# GPS_lte2.net
KiCad netlist of a schematic drawn in Altium Designer
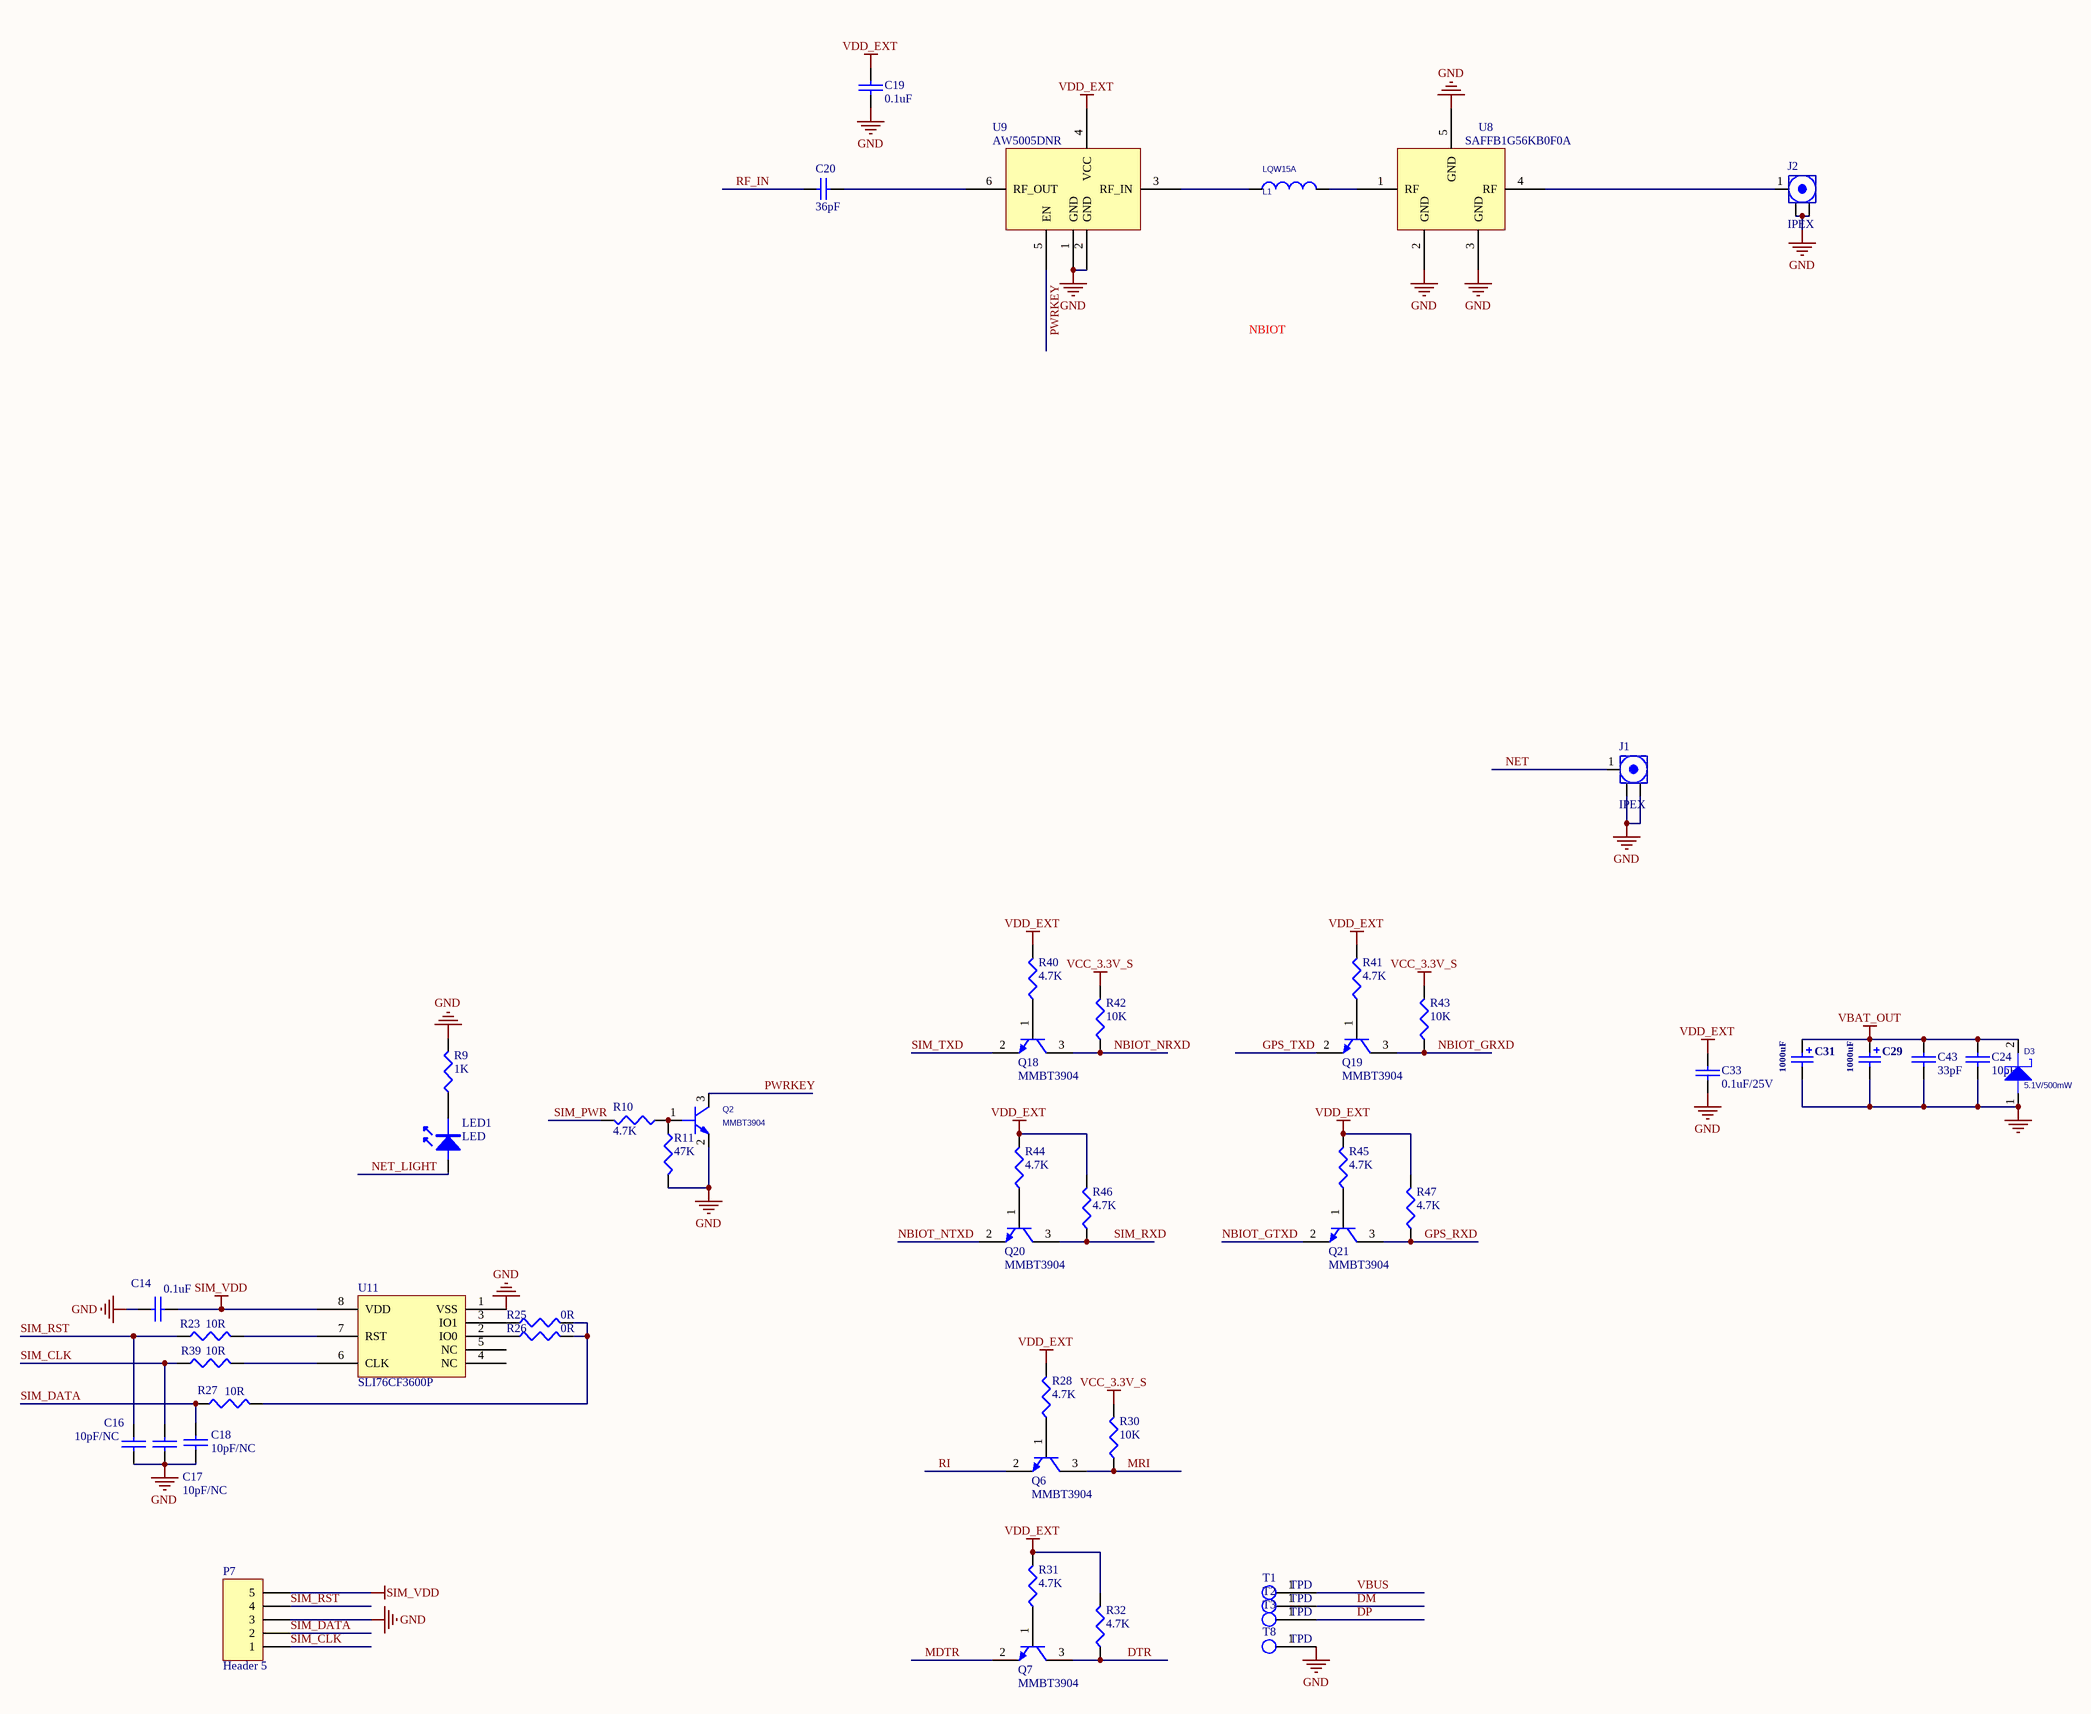
[diagram p0: GPS&&lte2.SchDoc]

(export (version "E")
  (design (tool "Eeschema 10.0.6"))
  (components
    (comp (ref "C14")
      (value "0.1uF")
      (footprint "0402C")
      (description "Capacitor")
      (libsource (lib "ZWLIntegrated_Library") (part "CAP"))
    )
    (comp (ref "C16")
      (value "10pF/NC")
      (footprint "0402C")
      (description "Capacitor")
      (libsource (lib "ZWLIntegrated_Library") (part "CAP"))
    )
    (comp (ref "C17")
      (value "10pF/NC")
      (footprint "0402C")
      (description "Capacitor")
      (libsource (lib "ZWLIntegrated_Library") (part "CAP"))
    )
    (comp (ref "C18")
      (value "10pF/NC")
      (footprint "0402C")
      (description "Capacitor")
      (libsource (lib "ZWLIntegrated_Library") (part "CAP"))
    )
    (comp (ref "C19")
      (value "0.1uF")
      (footprint "0402C")
      (description "Capacitor")
      (libsource (lib "ZWLIntegrated_Library") (part "CAP"))
    )
    (comp (ref "C20")
      (value "36pF")
      (footprint "0402c")
      (description "Capacitor")
      (fields (field (name "PUBLISHER") "Altium Limited"))
      (libsource (lib "Miscellaneous Devices") (part "Cap"))
    )
    (comp (ref "C24")
      (value "10pF")
      (footprint "0402C")
      (description "Capacitor")
      (libsource (lib "ZWLIntegrated_Library") (part "CAP"))
    )
    (comp (ref "C29")
      (value "1000uF")
      (footprint "7343")
      (description "Polarized Capacitor (Surface Mount)")
      (libsource (lib "KT_iBeacon") (part "Cap Pol3"))
    )
    (comp (ref "C31")
      (value "1000uF")
      (footprint "7343")
      (description "Polarized Capacitor (Surface Mount)")
      (libsource (lib "KT_iBeacon") (part "Cap Pol3"))
    )
    (comp (ref "C33")
      (value "0.1uF/25V")
      (footprint "0402C")
      (description "Capacitor")
      (libsource (lib "ZWLIntegrated_Library") (part "CAP"))
    )
    (comp (ref "C43")
      (value "33pF")
      (footprint "0402C")
      (description "Capacitor")
      (libsource (lib "ZWLIntegrated_Library") (part "CAP"))
    )
    (comp (ref "D3")
      (value "5.1V/500mW")
      (footprint "LL-34(D1206)")
      (fields (field (name "Comment") "DIODE_SCHOTTKY_0"))
      (libsource (lib "KT_iBeacon") (part "DIODE_SCHOTTKY_0"))
    )
    (comp (ref "J1") (value "IPEX") (footprint "RF-UFL") (libsource (lib "我的元件库") (part "ANT")))
    (comp (ref "J2") (value "IPEX") (footprint "RF-UFL") (libsource (lib "我的元件库") (part "ANT")))
    (comp (ref "L1") (value "LQW15A") (footprint "0402R") (libsource (lib "*") (part "INDUCTOR_1")))
    (comp (ref "LED1") (value "LED") (footprint "0603LED") (libsource (lib "我的元件库") (part "LED")))
    (comp (ref "P7")
      (value "Header 5")
      (footprint "5×1.25mmSMT")
      (description "Header, 5-Pin")
      (fields (field (name "PUBLISHER") "Altium Limited"))
      (libsource (lib "Miscellaneous Connectors") (part "Header 5"))
    )
    (comp (ref "Q2") (value "MMBT3904") (footprint "SOT23-3") (libsource (lib "*") (part "2N1069_1")))
    (comp (ref "Q6") (value "MMBT3904") (footprint "SOT23-3") (libsource (lib "Schlib1") (part "NPN")))
    (comp (ref "Q7") (value "MMBT3904") (footprint "SOT23-3") (libsource (lib "Schlib1") (part "NPN")))
    (comp (ref "Q18") (value "MMBT3904") (footprint "SOT23-3") (libsource (lib "Schlib1") (part "NPN")))
    (comp (ref "Q19") (value "MMBT3904") (footprint "SOT23-3") (libsource (lib "Schlib1") (part "NPN")))
    (comp (ref "Q20") (value "MMBT3904") (footprint "SOT23-3") (libsource (lib "Schlib1") (part "NPN")))
    (comp (ref "Q21") (value "MMBT3904") (footprint "SOT23-3") (libsource (lib "Schlib1") (part "NPN")))
    (comp (ref "R9") (value "1K") (footprint "0402R") (libsource (lib "ZWLIntegrated_Library") (part "RES1")))
    (comp (ref "R10")
      (value "4.7K")
      (footprint "0402R")
      (libsource (lib "ZWLIntegrated_Library") (part "RES1"))
    )
    (comp (ref "R11")
      (value "47K")
      (footprint "0402R")
      (libsource (lib "ZWLIntegrated_Library") (part "RES1"))
    )
    (comp (ref "R23")
      (value "10R")
      (footprint "0402R")
      (libsource (lib "ZWLIntegrated_Library") (part "RES1"))
    )
    (comp (ref "R25")
      (value "0R")
      (footprint "0402R")
      (libsource (lib "ZWLIntegrated_Library") (part "RES1"))
    )
    (comp (ref "R26")
      (value "0R")
      (footprint "0402R")
      (libsource (lib "ZWLIntegrated_Library") (part "RES1"))
    )
    (comp (ref "R27")
      (value "10R")
      (footprint "0402R")
      (libsource (lib "ZWLIntegrated_Library") (part "RES1"))
    )
    (comp (ref "R28")
      (value "4.7K")
      (footprint "0402R")
      (libsource (lib "ZWLIntegrated_Library") (part "RES1"))
    )
    (comp (ref "R30")
      (value "10K")
      (footprint "0402R")
      (libsource (lib "ZWLIntegrated_Library") (part "RES1"))
    )
    (comp (ref "R31")
      (value "4.7K")
      (footprint "0402R")
      (libsource (lib "ZWLIntegrated_Library") (part "RES1"))
    )
    (comp (ref "R32")
      (value "4.7K")
      (footprint "0402R")
      (libsource (lib "ZWLIntegrated_Library") (part "RES1"))
    )
    (comp (ref "R39")
      (value "10R")
      (footprint "0402R")
      (libsource (lib "ZWLIntegrated_Library") (part "RES1"))
    )
    (comp (ref "R40")
      (value "4.7K")
      (footprint "0402R")
      (libsource (lib "ZWLIntegrated_Library") (part "RES1"))
    )
    (comp (ref "R41")
      (value "4.7K")
      (footprint "0402R")
      (libsource (lib "ZWLIntegrated_Library") (part "RES1"))
    )
    (comp (ref "R42")
      (value "10K")
      (footprint "0402R")
      (libsource (lib "ZWLIntegrated_Library") (part "RES1"))
    )
    (comp (ref "R43")
      (value "10K")
      (footprint "0402R")
      (libsource (lib "ZWLIntegrated_Library") (part "RES1"))
    )
    (comp (ref "R44")
      (value "4.7K")
      (footprint "0402R")
      (libsource (lib "ZWLIntegrated_Library") (part "RES1"))
    )
    (comp (ref "R45")
      (value "4.7K")
      (footprint "0402R")
      (libsource (lib "ZWLIntegrated_Library") (part "RES1"))
    )
    (comp (ref "R46")
      (value "4.7K")
      (footprint "0402R")
      (libsource (lib "ZWLIntegrated_Library") (part "RES1"))
    )
    (comp (ref "R47")
      (value "4.7K")
      (footprint "0402R")
      (libsource (lib "ZWLIntegrated_Library") (part "RES1"))
    )
    (comp (ref "T1") (value "TPD") (footprint "TPD") (libsource (lib "stm32") (part "TPD")))
    (comp (ref "T2") (value "TPD") (footprint "TPD") (libsource (lib "stm32") (part "TPD")))
    (comp (ref "T3") (value "TPD") (footprint "TPD") (libsource (lib "stm32") (part "TPD")))
    (comp (ref "T8") (value "TPD") (footprint "TPD") (libsource (lib "stm32") (part "TPD")))
    (comp (ref "U8")
      (value "SAFFB1G56KB0F0A")
      (footprint "SAFFB1G56KB0F0A")
      (libsource (lib "stm32") (part "SAFFB1G56KBOFA"))
    )
    (comp (ref "U9") (value "AW5005DNR") (footprint "AW5005") (libsource (lib "stm32") (part "AW5005DNR")))
    (comp (ref "U11")
      (value "SLI76CF3600P")
      (footprint "QFN127P500X600X80-8N")
      (libsource (lib "stm32") (part "SLI76CF3600P"))
    )
  )
  (nets
    (net (code "1") (name "/DM") (class "Default") (node (ref "T2") (pin "1") (pintype "passive")))
    (net (code "2") (name "/DP") (class "Default") (node (ref "T3") (pin "1") (pintype "passive")))
    (net (code "3") (name "/DTR") (class "Default")
      (node (ref "Q7") (pin "3") (pinfunction "C_3") (pintype "passive"))
      (node (ref "R32") (pin "1") (pinfunction "1_1") (pintype "passive"))
    )
    (net (code "4") (name "/GPS_RXD") (class "Default")
      (node (ref "Q21") (pin "3") (pinfunction "C_3") (pintype "passive"))
      (node (ref "R47") (pin "1") (pinfunction "1_1") (pintype "passive"))
    )
    (net (code "5") (name "/GPS_TXD") (class "Default")
      (node (ref "Q19") (pin "2") (pinfunction "E_2") (pintype "passive"))
    )
    (net (code "6") (name "/MDTR") (class "Default")
      (node (ref "Q7") (pin "2") (pinfunction "E_2") (pintype "passive"))
    )
    (net (code "7") (name "/MRI") (class "Default")
      (node (ref "Q6") (pin "3") (pinfunction "C_3") (pintype "passive"))
      (node (ref "R30") (pin "1") (pinfunction "1_1") (pintype "passive"))
    )
    (net (code "8") (name "/NBIOT_GRXD") (class "Default")
      (node (ref "Q19") (pin "3") (pinfunction "C_3") (pintype "passive"))
      (node (ref "R43") (pin "1") (pinfunction "1_1") (pintype "passive"))
    )
    (net (code "9") (name "/NBIOT_GTXD") (class "Default")
      (node (ref "Q21") (pin "2") (pinfunction "E_2") (pintype "passive"))
    )
    (net (code "10") (name "/NBIOT_NRXD") (class "Default")
      (node (ref "Q18") (pin "3") (pinfunction "C_3") (pintype "passive"))
      (node (ref "R42") (pin "1") (pinfunction "1_1") (pintype "passive"))
    )
    (net (code "11") (name "/NBIOT_NTXD") (class "Default")
      (node (ref "Q20") (pin "2") (pinfunction "E_2") (pintype "passive"))
    )
    (net (code "12") (name "/NET") (class "Default")
      (node (ref "J1") (pin "1") (pinfunction "X_1") (pintype "passive"))
    )
    (net (code "13") (name "/NET_LIGHT") (class "Default")
      (node (ref "LED1") (pin "1") (pinfunction "1_1") (pintype "passive"))
    )
    (net (code "14") (name "/PWRKEY") (class "Default")
      (node (ref "Q2") (pin "3") (pinfunction "C_3") (pintype "passive"))
      (node (ref "U9") (pin "5") (pinfunction "EN_5") (pintype "passive"))
    )
    (net (code "15") (name "/RF_IN") (class "Default")
      (node (ref "C20") (pin "1") (pinfunction "1_1") (pintype "passive"))
    )
    (net (code "16") (name "/RI") (class "Default")
      (node (ref "Q6") (pin "2") (pinfunction "E_2") (pintype "passive"))
    )
    (net (code "17") (name "/SIM_CLK") (class "Default")
      (node (ref "C17") (pin "2") (pinfunction "2_2") (pintype "passive"))
      (node (ref "P7") (pin "1") (pinfunction "1_1") (pintype "passive"))
      (node (ref "R39") (pin "1") (pinfunction "1_1") (pintype "passive"))
    )
    (net (code "18") (name "/SIM_DATA") (class "Default")
      (node (ref "C18") (pin "2") (pinfunction "2_2") (pintype "passive"))
      (node (ref "P7") (pin "2") (pinfunction "2_2") (pintype "passive"))
      (node (ref "R27") (pin "1") (pinfunction "1_1") (pintype "passive"))
    )
    (net (code "19") (name "/SIM_PWR") (class "Default")
      (node (ref "R10") (pin "2") (pinfunction "2_2") (pintype "passive"))
    )
    (net (code "20") (name "/SIM_RST") (class "Default")
      (node (ref "C16") (pin "2") (pinfunction "2_2") (pintype "passive"))
      (node (ref "P7") (pin "4") (pinfunction "4_4") (pintype "passive"))
      (node (ref "R23") (pin "1") (pinfunction "1_1") (pintype "passive"))
    )
    (net (code "21") (name "/SIM_RXD") (class "Default")
      (node (ref "Q20") (pin "3") (pinfunction "C_3") (pintype "passive"))
      (node (ref "R46") (pin "1") (pinfunction "1_1") (pintype "passive"))
    )
    (net (code "22") (name "/SIM_TXD") (class "Default")
      (node (ref "Q18") (pin "2") (pinfunction "E_2") (pintype "passive"))
    )
    (net (code "23") (name "/VBUS") (class "Default") (node (ref "T1") (pin "1") (pintype "passive")))
    (net (code "24") (name "GND") (class "Default")
      (node (ref "C14") (pin "1") (pinfunction "1_1") (pintype "passive"))
      (node (ref "C16") (pin "1") (pinfunction "1_1") (pintype "passive"))
      (node (ref "C17") (pin "1") (pinfunction "1_1") (pintype "passive"))
      (node (ref "C18") (pin "1") (pinfunction "1_1") (pintype "passive"))
      (node (ref "C19") (pin "1") (pinfunction "1_1") (pintype "passive"))
      (node (ref "C24") (pin "1") (pinfunction "1_1") (pintype "passive"))
      (node (ref "C29") (pin "2") (pinfunction "2_2") (pintype "passive"))
      (node (ref "C31") (pin "2") (pinfunction "2_2") (pintype "passive"))
      (node (ref "C33") (pin "1") (pinfunction "1_1") (pintype "passive"))
      (node (ref "C43") (pin "1") (pinfunction "1_1") (pintype "passive"))
      (node (ref "D3") (pin "1") (pinfunction "1_1") (pintype "passive"))
      (node (ref "J1") (pin "2") (pinfunction "Y_2") (pintype "passive"))
      (node (ref "J2") (pin "2") (pinfunction "Y_2") (pintype "passive"))
      (node (ref "P7") (pin "3") (pinfunction "3_3") (pintype "passive"))
      (node (ref "Q2") (pin "2") (pinfunction "E_2") (pintype "passive"))
      (node (ref "R11") (pin "2") (pinfunction "2_2") (pintype "passive"))
      (node (ref "R9") (pin "2") (pinfunction "2_2") (pintype "passive"))
      (node (ref "T8") (pin "1") (pintype "passive"))
      (node (ref "U11") (pin "1") (pinfunction "VSS_1") (pintype "passive"))
      (node (ref "U8") (pin "2") (pinfunction "GND_2") (pintype "passive"))
      (node (ref "U8") (pin "3") (pinfunction "GND_3") (pintype "passive"))
      (node (ref "U8") (pin "5") (pinfunction "GND_5") (pintype "passive"))
      (node (ref "U9") (pin "1") (pinfunction "GND_1") (pintype "passive"))
      (node (ref "U9") (pin "2") (pinfunction "GND_2") (pintype "passive"))
    )
    (net (code "25") (name "Net-(J2-X)") (class "Default")
      (node (ref "J2") (pin "1") (pinfunction "X_1") (pintype "passive"))
      (node (ref "U8") (pin "4") (pinfunction "RF_4") (pintype "passive"))
    )
    (net (code "26") (name "Net-(L1-Pad2)") (class "Default")
      (node (ref "L1") (pin "2") (pinfunction "2_2") (pintype "passive"))
      (node (ref "U8") (pin "1") (pinfunction "RF_1") (pintype "passive"))
    )
    (net (code "27") (name "Net-(LED1-Pad2)") (class "Default")
      (node (ref "LED1") (pin "2") (pinfunction "2_2") (pintype "passive"))
      (node (ref "R9") (pin "1") (pinfunction "1_1") (pintype "passive"))
    )
    (net (code "28") (name "Net-(Q2-B)") (class "Default")
      (node (ref "Q2") (pin "1") (pinfunction "B_1") (pintype "passive"))
      (node (ref "R10") (pin "1") (pinfunction "1_1") (pintype "passive"))
      (node (ref "R11") (pin "1") (pinfunction "1_1") (pintype "passive"))
    )
    (net (code "29") (name "Net-(Q6-B)") (class "Default")
      (node (ref "Q6") (pin "1") (pinfunction "B_1") (pintype "passive"))
      (node (ref "R28") (pin "1") (pinfunction "1_1") (pintype "passive"))
    )
    (net (code "30") (name "Net-(Q7-B)") (class "Default")
      (node (ref "Q7") (pin "1") (pinfunction "B_1") (pintype "passive"))
      (node (ref "R31") (pin "1") (pinfunction "1_1") (pintype "passive"))
    )
    (net (code "31") (name "Net-(Q18-B)") (class "Default")
      (node (ref "Q18") (pin "1") (pinfunction "B_1") (pintype "passive"))
      (node (ref "R40") (pin "1") (pinfunction "1_1") (pintype "passive"))
    )
    (net (code "32") (name "Net-(Q19-B)") (class "Default")
      (node (ref "Q19") (pin "1") (pinfunction "B_1") (pintype "passive"))
      (node (ref "R41") (pin "1") (pinfunction "1_1") (pintype "passive"))
    )
    (net (code "33") (name "Net-(Q20-B)") (class "Default")
      (node (ref "Q20") (pin "1") (pinfunction "B_1") (pintype "passive"))
      (node (ref "R44") (pin "1") (pinfunction "1_1") (pintype "passive"))
    )
    (net (code "34") (name "Net-(Q21-B)") (class "Default")
      (node (ref "Q21") (pin "1") (pinfunction "B_1") (pintype "passive"))
      (node (ref "R45") (pin "1") (pinfunction "1_1") (pintype "passive"))
    )
    (net (code "35") (name "Net-(R25-Pad2)") (class "Default")
      (node (ref "R25") (pin "2") (pinfunction "2_2") (pintype "passive"))
      (node (ref "R26") (pin "2") (pinfunction "2_2") (pintype "passive"))
      (node (ref "R27") (pin "2") (pinfunction "2_2") (pintype "passive"))
    )
    (net (code "36") (name "Net-(U9-RF_IN)") (class "Default")
      (node (ref "L1") (pin "1") (pinfunction "1_1") (pintype "passive"))
      (node (ref "U9") (pin "3") (pinfunction "RF_IN_3") (pintype "passive"))
    )
    (net (code "37") (name "Net-(U9-RF_OUT)") (class "Default")
      (node (ref "C20") (pin "2") (pinfunction "2_2") (pintype "passive"))
      (node (ref "U9") (pin "6") (pinfunction "RF_OUT_6") (pintype "passive"))
    )
    (net (code "38") (name "Net-(U11-CLK)") (class "Default")
      (node (ref "R39") (pin "2") (pinfunction "2_2") (pintype "passive"))
      (node (ref "U11") (pin "6") (pinfunction "CLK_6") (pintype "passive"))
    )
    (net (code "39") (name "Net-(U11-IO0)") (class "Default")
      (node (ref "R26") (pin "1") (pinfunction "1_1") (pintype "passive"))
      (node (ref "U11") (pin "2") (pinfunction "IO0_2") (pintype "passive"))
    )
    (net (code "40") (name "Net-(U11-IO1)") (class "Default")
      (node (ref "R25") (pin "1") (pinfunction "1_1") (pintype "passive"))
      (node (ref "U11") (pin "3") (pinfunction "IO1_3") (pintype "passive"))
    )
    (net (code "41") (name "Net-(U11-RST)") (class "Default")
      (node (ref "R23") (pin "2") (pinfunction "2_2") (pintype "passive"))
      (node (ref "U11") (pin "7") (pinfunction "RST_7") (pintype "passive"))
    )
    (net (code "42") (name "SIM_VDD") (class "Default")
      (node (ref "C14") (pin "2") (pinfunction "2_2") (pintype "passive"))
      (node (ref "P7") (pin "5") (pinfunction "5_5") (pintype "passive"))
      (node (ref "U11") (pin "8") (pinfunction "VDD_8") (pintype "passive"))
    )
    (net (code "43") (name "VBAT_OUT") (class "Default")
      (node (ref "C24") (pin "2") (pinfunction "2_2") (pintype "passive"))
      (node (ref "C29") (pin "1") (pinfunction "1_1") (pintype "passive"))
      (node (ref "C31") (pin "1") (pinfunction "1_1") (pintype "passive"))
      (node (ref "C43") (pin "2") (pinfunction "2_2") (pintype "passive"))
      (node (ref "D3") (pin "2") (pinfunction "2_2") (pintype "passive"))
    )
    (net (code "44") (name "VCC_3.3V_S") (class "Default")
      (node (ref "R30") (pin "2") (pinfunction "2_2") (pintype "passive"))
      (node (ref "R42") (pin "2") (pinfunction "2_2") (pintype "passive"))
      (node (ref "R43") (pin "2") (pinfunction "2_2") (pintype "passive"))
    )
    (net (code "45") (name "VDD_EXT") (class "Default")
      (node (ref "C19") (pin "2") (pinfunction "2_2") (pintype "passive"))
      (node (ref "C33") (pin "2") (pinfunction "2_2") (pintype "passive"))
      (node (ref "R28") (pin "2") (pinfunction "2_2") (pintype "passive"))
      (node (ref "R31") (pin "2") (pinfunction "2_2") (pintype "passive"))
      (node (ref "R32") (pin "2") (pinfunction "2_2") (pintype "passive"))
      (node (ref "R40") (pin "2") (pinfunction "2_2") (pintype "passive"))
      (node (ref "R41") (pin "2") (pinfunction "2_2") (pintype "passive"))
      (node (ref "R44") (pin "2") (pinfunction "2_2") (pintype "passive"))
      (node (ref "R45") (pin "2") (pinfunction "2_2") (pintype "passive"))
      (node (ref "R46") (pin "2") (pinfunction "2_2") (pintype "passive"))
      (node (ref "R47") (pin "2") (pinfunction "2_2") (pintype "passive"))
      (node (ref "U9") (pin "4") (pinfunction "VCC_4") (pintype "passive"))
    )
    (net (code "46") (name "unconnected-(U11-NC-Pad4)") (class "Default")
      (node (ref "U11") (pin "4") (pinfunction "NC_4") (pintype "passive"))
    )
    (net (code "47") (name "unconnected-(U11-NC-Pad5)") (class "Default")
      (node (ref "U11") (pin "5") (pinfunction "NC_5") (pintype "passive"))
    )
  )
)
